# Schematics.net
KiCad netlist of a schematic drawn in Altium Designer
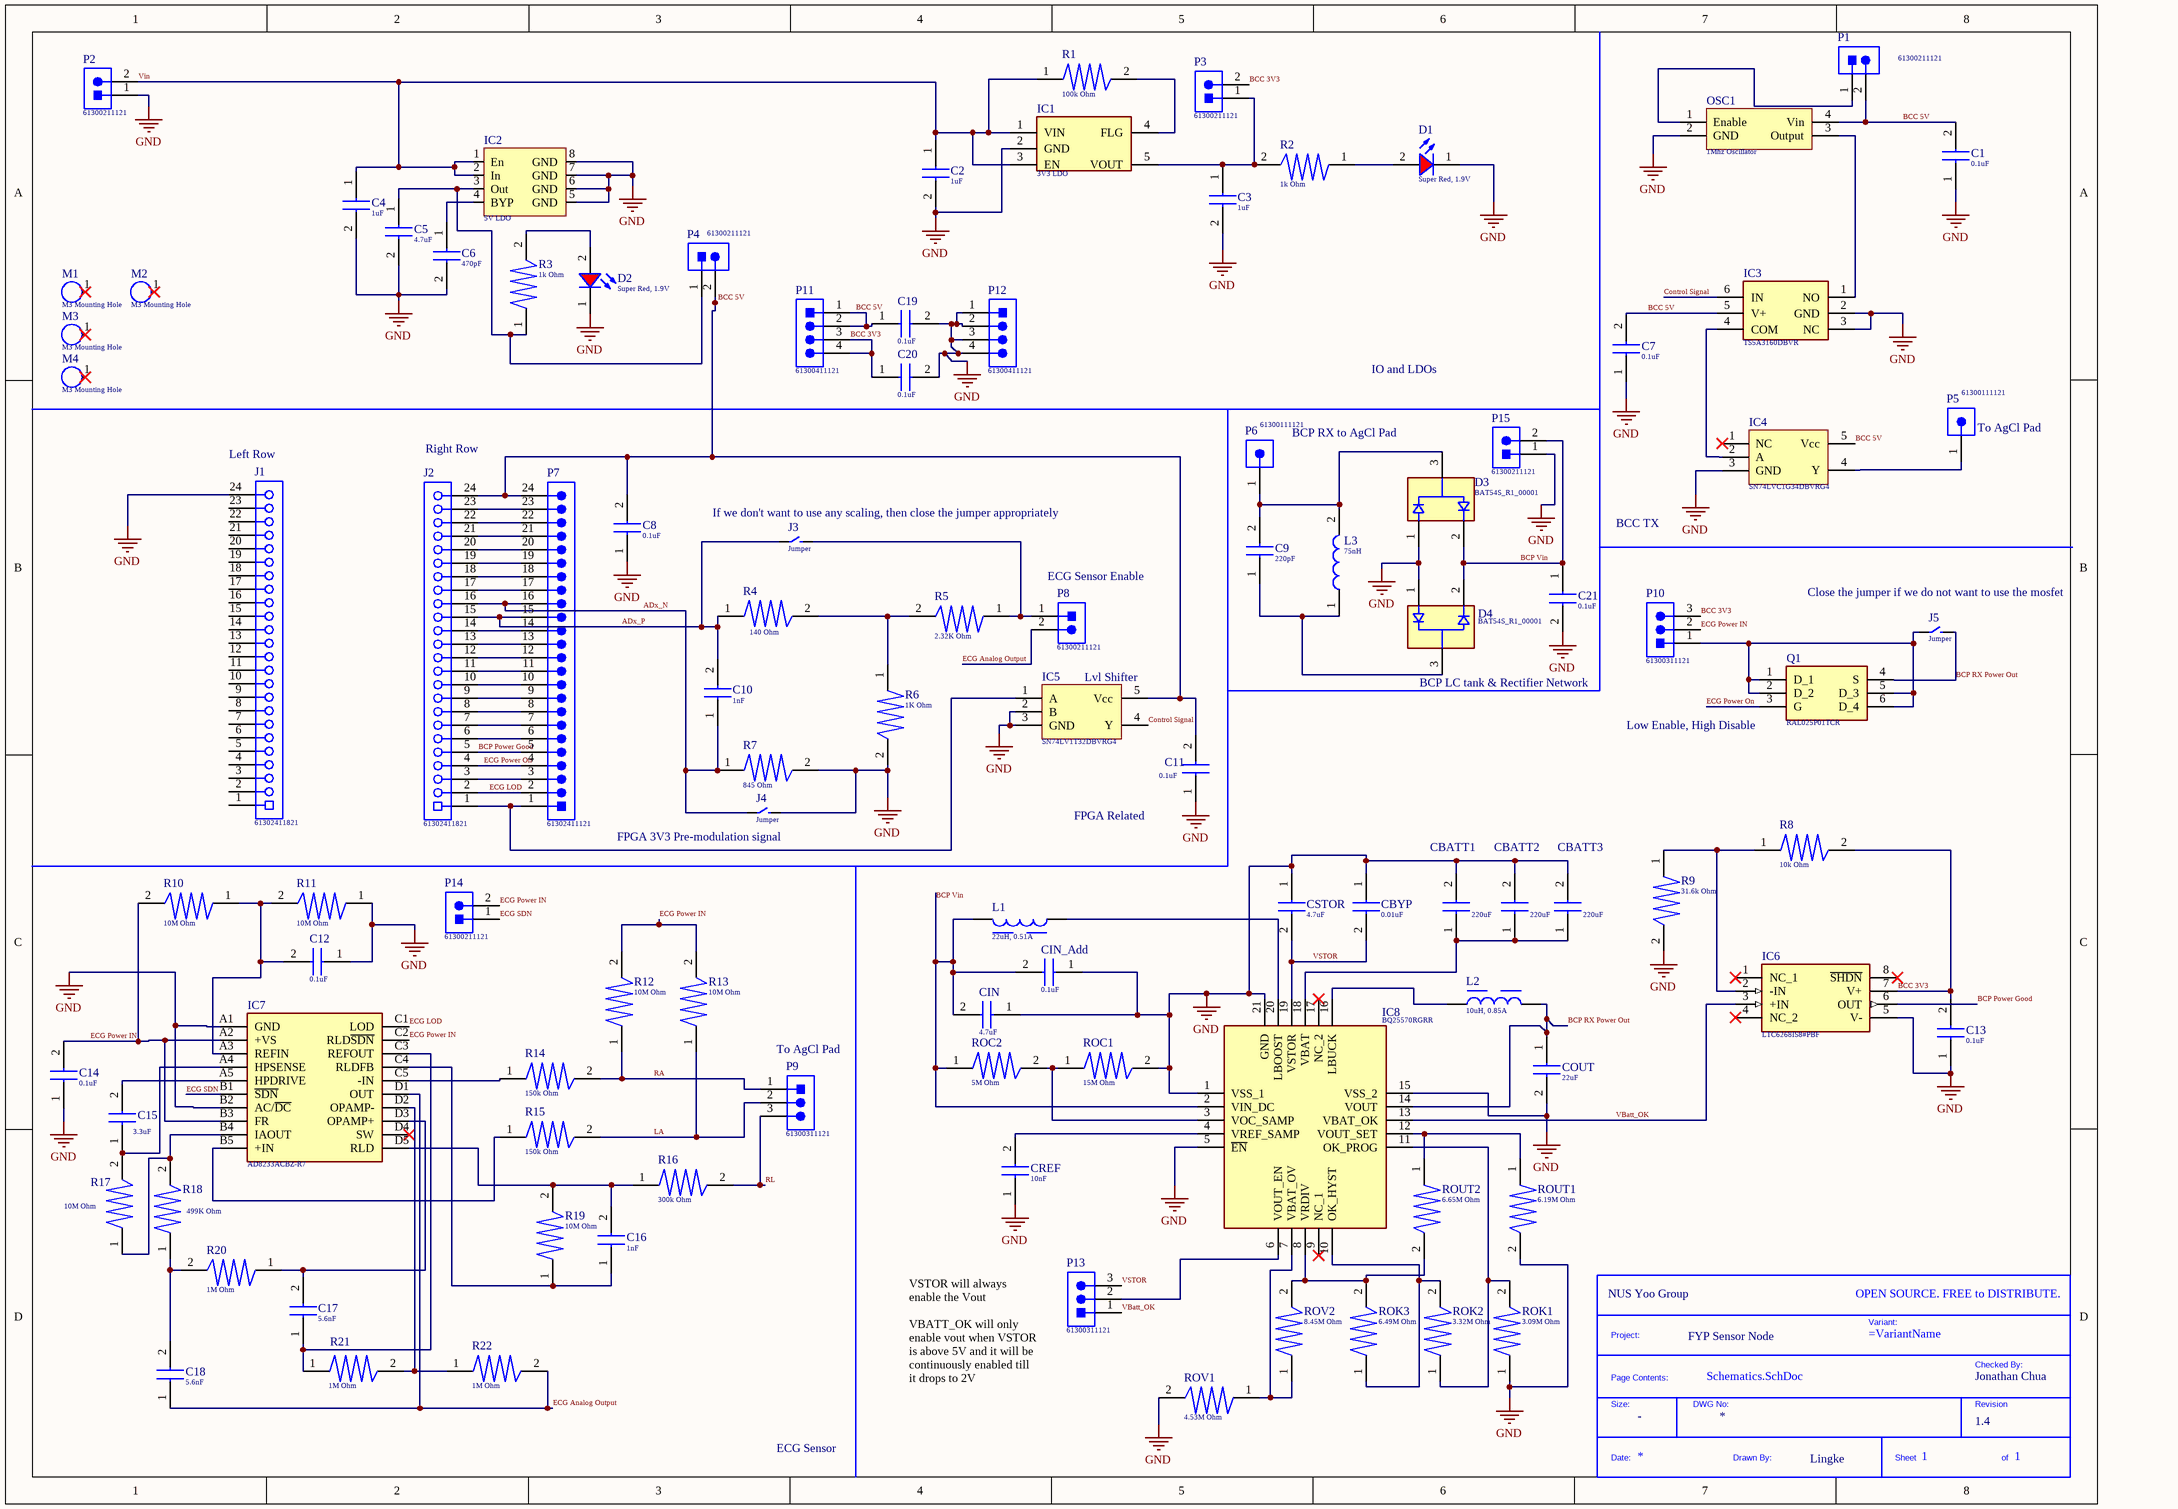
[diagram p0: Schematics.SchDoc]

(export (version "E")
  (design (tool "Eeschema 10.0.6"))
  (components
    (comp (ref "*")
      (value "Title_Block")
      (description "Standard Title Block.")
      (fields
        (field (name "PROJECT NAME") "FYP Sensor Node")
        (field (name "COMPANY") "NUS Yoo Group")
        (field (name "DRAWN BY") "Lingke")
        (field (name "REVISION") "1.4")
        (field (name "DWG NO") "*")
        (field (name "SIZE") "-")
        (field (name "CHECKED BY") "Jonathan Chua")
      )
      (libsource (lib "General Electronics") (part "Title_Block"))
    )
    (comp (ref "C1")
      (value "0.1uF")
      (footprint "0603")
      (description "Capacitor")
      (libsource (lib "General Electronics") (part "Capacitor_0603"))
    )
    (comp (ref "C2")
      (value "1uF")
      (footprint "0603")
      (description "Capacitor")
      (libsource (lib "General Electronics") (part "Capacitor_0603"))
    )
    (comp (ref "C3")
      (value "1uF")
      (footprint "0603")
      (description "Capacitor")
      (libsource (lib "General Electronics") (part "Capacitor_0603"))
    )
    (comp (ref "C4")
      (value "1uF")
      (footprint "0603")
      (description "Capacitor")
      (libsource (lib "General Electronics") (part "Capacitor_0603"))
    )
    (comp (ref "C5")
      (value "4.7uF")
      (footprint "0603")
      (description "Capacitor")
      (libsource (lib "General Electronics") (part "Capacitor_0603"))
    )
    (comp (ref "C6")
      (value "470pF")
      (footprint "0603")
      (description "Capacitor")
      (libsource (lib "General Electronics") (part "Capacitor_0603"))
    )
    (comp (ref "C7")
      (value "0.1uF")
      (footprint "0603")
      (description "Capacitor")
      (libsource (lib "General Electronics") (part "Capacitor_0603"))
    )
    (comp (ref "C8")
      (value "0.1uF")
      (footprint "0603")
      (description "Capacitor")
      (libsource (lib "General Electronics") (part "Capacitor_0603"))
    )
    (comp (ref "C9")
      (value "220pF")
      (footprint "0603")
      (description "Capacitor")
      (libsource (lib "General Electronics") (part "Capacitor_0603"))
    )
    (comp (ref "C10")
      (value "1nF")
      (footprint "0603")
      (description "Capacitor")
      (libsource (lib "General Electronics") (part "Capacitor_0603"))
    )
    (comp (ref "C11")
      (value "0.1uF")
      (footprint "0603")
      (description "Capacitor")
      (libsource (lib "General Electronics") (part "Capacitor_0603"))
    )
    (comp (ref "C12")
      (value "0.1uF")
      (footprint "0603")
      (description "Capacitor")
      (libsource (lib "General Electronics") (part "Capacitor_0603"))
    )
    (comp (ref "C13")
      (value "0.1uF")
      (footprint "0603")
      (description "Capacitor")
      (libsource (lib "General Electronics") (part "Capacitor_0603"))
    )
    (comp (ref "C14")
      (value "0.1uF")
      (footprint "0603")
      (description "Capacitor")
      (libsource (lib "General Electronics") (part "Capacitor_0603"))
    )
    (comp (ref "C15")
      (value "3.3uF")
      (footprint "0603")
      (description "Capacitor")
      (libsource (lib "General Electronics") (part "Capacitor_0603"))
    )
    (comp (ref "C16")
      (value "1nF")
      (footprint "0603")
      (description "Capacitor")
      (libsource (lib "General Electronics") (part "Capacitor_0603"))
    )
    (comp (ref "C17")
      (value "5.6nF")
      (footprint "0603")
      (description "Capacitor")
      (libsource (lib "General Electronics") (part "Capacitor_0603"))
    )
    (comp (ref "C18")
      (value "5.6nF")
      (footprint "0603")
      (description "Capacitor")
      (libsource (lib "General Electronics") (part "Capacitor_0603"))
    )
    (comp (ref "C19")
      (value "0.1uF")
      (footprint "0603")
      (description "Capacitor")
      (libsource (lib "General Electronics") (part "Capacitor_0603"))
    )
    (comp (ref "C20")
      (value "0.1uF")
      (footprint "0603")
      (description "Capacitor")
      (libsource (lib "General Electronics") (part "Capacitor_0603"))
    )
    (comp (ref "C21")
      (value "0.1uF")
      (footprint "0603")
      (description "Capacitor")
      (libsource (lib "General Electronics") (part "Capacitor_0603"))
    )
    (comp (ref "CBATT1")
      (value "220uF")
      (footprint "1206")
      (description "Capacitor")
      (libsource (lib "General Electronics") (part "Capacitor_1206"))
    )
    (comp (ref "CBATT2")
      (value "220uF")
      (footprint "1206")
      (description "Capacitor")
      (libsource (lib "General Electronics") (part "Capacitor_1206"))
    )
    (comp (ref "CBATT3")
      (value "220uF")
      (footprint "1206")
      (description "Capacitor")
      (libsource (lib "General Electronics") (part "Capacitor_1206"))
    )
    (comp (ref "CBYP")
      (value "0.01uF")
      (footprint "0603")
      (description "Capacitor")
      (libsource (lib "General Electronics") (part "Capacitor_0603"))
    )
    (comp (ref "CIN")
      (value "4.7uF")
      (footprint "0603")
      (description "Capacitor")
      (libsource (lib "General Electronics") (part "Capacitor_0603"))
    )
    (comp (ref "CIN_Add")
      (value "0.1uF")
      (footprint "0603")
      (description "Capacitor")
      (libsource (lib "General Electronics") (part "Capacitor_0603"))
    )
    (comp (ref "COUT")
      (value "22uF")
      (footprint "0603")
      (description "Capacitor")
      (libsource (lib "General Electronics") (part "Capacitor_0603"))
    )
    (comp (ref "CREF")
      (value "10nF")
      (footprint "0603")
      (description "Capacitor")
      (libsource (lib "General Electronics") (part "Capacitor_0603"))
    )
    (comp (ref "CSTOR")
      (value "4.7uF")
      (footprint "0603")
      (description "Capacitor")
      (libsource (lib "General Electronics") (part "Capacitor_0603"))
    )
    (comp (ref "D1")
      (value "Super Red, 1.9V")
      (footprint "WL-SMCW_0603_H=0.7mm")
      (description "WL-SMCW SMT Mono-color Chip LED Waterclear, size 0603, Super Red, 1.9V, 140deg")
      (fields (field (name "PART NUMBER") "150060SS75000") (field (name "PUBLISHER") "Wurth Elektronik"))
      (libsource (lib "Altium_WL-SMCW (rev20a)") (part "150060SS75000"))
    )
    (comp (ref "D2")
      (value "Super Red, 1.9V")
      (footprint "WL-SMCW_0603_H=0.7mm")
      (description "WL-SMCW SMT Mono-color Chip LED Waterclear, size 0603, Super Red, 1.9V, 140deg")
      (fields (field (name "PART NUMBER") "150060SS75000") (field (name "PUBLISHER") "Wurth Elektronik"))
      (libsource (lib "Altium_WL-SMCW (rev20a)") (part "150060SS75000"))
    )
    (comp (ref "D3")
      (value "BAT54S_R1_00001")
      (footprint "SOT95P240X110-3N")
      (description "Schottky Diode")
      (libsource (lib "") (part "BAT54S_R1_00001_1"))
    )
    (comp (ref "D4")
      (value "BAT54S_R1_00001")
      (footprint "SOT95P240X110-3N")
      (description "Schottky Diode")
      (libsource (lib "FYP_BCC_BCP NUS") (part "BAT54S_R1_00001"))
    )
    (comp (ref "IC1")
      (value "3V3 LDO")
      (footprint "SOT-23-5")
      (description "Power Supply")
      (fields
        (field (name "MOUSER2 PART NUMBER") "998-MIC5317-3.3YM5TR")
        (field (name "MANUFACTURER_PART_NUMBER") "MIC5317-3.3YM5-TR")
      )
      (libsource (lib "FYP_BCC_BCP NUS") (part "MIC5216-3.3YM5-TR"))
    )
    (comp (ref "IC2")
      (value "5V LDO")
      (footprint "MSOP-8_MS")
      (libsource (lib "FYP_BCC_BCP NUS") (part "MIC5219-5.0YMM-TR"))
    )
    (comp (ref "IC3")
      (value "TS5A3160DBVR")
      (footprint "SOT-23-6")
      (description "Integrated Circuit")
      (fields (field (name "MOUSER2 PART NUMBER") "595-TS5A3160DBVR"))
      (libsource (lib "FYP_BCC_BCP NUS") (part "TS5A3160DBVR"))
    )
    (comp (ref "IC4")
      (value "SN74LVC1G34DBVRG4")
      (footprint "SOT-23-5")
      (libsource (lib "FYP_BCC_BCP NUS") (part "SN74LVC1G34DBVRG4"))
    )
    (comp (ref "IC5")
      (value "SN74LV1T32DBVRG4")
      (footprint "SOT-23-5")
      (libsource (lib "FYP_BCC_BCP NUS") (part "SN74LV1T32DBVRG4"))
    )
    (comp (ref "IC6")
      (value "LTC6268IS8#PBF")
      (footprint "SOIC127P599X175-8N")
      (description "Integrated Circuit")
      (fields (field (name "MOUSER2 PART NUMBER") "584-LTC6268IS8#PBF"))
      (libsource (lib "FYP_BCC_BCP NUS") (part "LTC6268IS8#PBF"))
    )
    (comp (ref "IC7")
      (value "AD8233ACBZ-R7")
      (footprint "BGA20C40P5X4_204X170X56")
      (description "Integrated Circuit")
      (libsource (lib "FYP_BCC_BCP NUS") (part "AD8233ACBZ-R7"))
    )
    (comp (ref "IC8")
      (value "BQ25570RGRR")
      (footprint "QFN50P350X350X100-21N-D")
      (description "Integrated Circuit")
      (fields (field (name "MOUSER2 PART NUMBER") "595-BQ25570RGRR"))
      (libsource (lib "FYP_BCC_BCP NUS") (part "BQ25570RGRR"))
    )
    (comp (ref "J1")
      (value "61302411821")
      (footprint "61302411821")
      (description "WR-PHD Socket Header, THT, pitch 2.54mm, Single Row, Vertical, 24p")
      (fields (field (name "MANUFACTURER") "Wurth Elektronik"))
      (libsource (lib "Altium_WR-PHD (rev22a)") (part "61302411821"))
    )
    (comp (ref "J2")
      (value "61302411821")
      (footprint "61302411821")
      (description "WR-PHD Socket Header, THT, pitch 2.54mm, Single Row, Vertical, 24p")
      (fields (field (name "MANUFACTURER") "Wurth Elektronik"))
      (libsource (lib "Altium_WR-PHD (rev22a)") (part "61302411821"))
    )
    (comp (ref "J3")
      (value "Jumper")
      (footprint "0603")
      (description "Capacitor")
      (libsource (lib "General Electronics") (part "0603_Jumper"))
    )
    (comp (ref "J4")
      (value "Jumper")
      (footprint "0603")
      (description "Capacitor")
      (libsource (lib "General Electronics") (part "0603_Jumper"))
    )
    (comp (ref "J5")
      (value "Jumper")
      (footprint "0603")
      (description "Capacitor")
      (libsource (lib "General Electronics") (part "0603_Jumper"))
    )
    (comp (ref "L1")
      (value "22uH, 0.51A")
      (footprint "WE-TPC_3816")
      (description "WE-TPC SMT Tiny Power Inductor, size 3816, 22uH, 0.51A, 450mOhm")
      (fields
        (field (name "MANUFACTURER") "Wurth Elektronik")
        (field (name "MANUFACTURER PART NUMBER") "744031220")
      )
      (libsource (lib "WE-TPC (rev22a)") (part "744031220"))
    )
    (comp (ref "L2")
      (value "10uH, 0.85A")
      (footprint "WE-MAPI_3015")
      (description "WE-MAPI SMT Power Inductor, size 3015, 10uH, 0.85A")
      (fields
        (field (name "MANUFACTURER") "Wurth Elektronik")
        (field (name "MANUFACTURER PART NUMBER") "74438335100")
      )
      (libsource (lib "WE-MAPI (rev22a)") (part "74438335100"))
    )
    (comp (ref "L3")
      (value "75nH")
      (footprint "0603")
      (description "Inductor")
      (libsource (lib "General Electronics") (part "Inductor_0603"))
    )
    (comp (ref "M1")
      (value "M3 Mounting Hole")
      (footprint "M3 Hole")
      (libsource (lib "General Electronics") (part "M3_Mounting_hole"))
    )
    (comp (ref "M2")
      (value "M3 Mounting Hole")
      (footprint "M3 Hole")
      (libsource (lib "General Electronics") (part "M3_Mounting_hole"))
    )
    (comp (ref "M3")
      (value "M3 Mounting Hole")
      (footprint "M3 Hole")
      (libsource (lib "General Electronics") (part "M3_Mounting_hole"))
    )
    (comp (ref "M4")
      (value "M3 Mounting Hole")
      (footprint "M3 Hole")
      (libsource (lib "General Electronics") (part "M3_Mounting_hole"))
    )
    (comp (ref "OSC1")
      (value "1Mhz Oscillator")
      (footprint "CB3-3I-4M0000")
      (libsource (lib "FYP_BCC_BCP NUS") (part "LFSPXO053327Bulk"))
    )
    (comp (ref "P1")
      (value "61300211121")
      (footprint "61300211121")
      (description "WR-PHD Pin Header, THT, pitch 2.54mm, Single Row, Vertical, 2p")
      (fields (field (name "MANUFACTURER") "Wurth Elektronik"))
      (libsource (lib "") (part "61300211121_1"))
    )
    (comp (ref "P2")
      (value "61300211121")
      (footprint "61300211121")
      (description "WR-PHD Pin Header, THT, pitch 2.54mm, Single Row, Vertical, 2p")
      (fields (field (name "MANUFACTURER") "Wurth Elektronik"))
      (libsource (lib "Altium_WR-PHD (rev22a)") (part "61300211121"))
    )
    (comp (ref "P3")
      (value "61300211121")
      (footprint "61300211121")
      (description "WR-PHD Pin Header, THT, pitch 2.54mm, Single Row, Vertical, 2p")
      (fields (field (name "MANUFACTURER") "Wurth Elektronik"))
      (libsource (lib "Altium_WR-PHD (rev22a)") (part "61300211121"))
    )
    (comp (ref "P4")
      (value "61300211121")
      (footprint "61300211121")
      (description "WR-PHD Pin Header, THT, pitch 2.54mm, Single Row, Vertical, 2p")
      (fields (field (name "MANUFACTURER") "Wurth Elektronik"))
      (libsource (lib "") (part "61300211121_1"))
    )
    (comp (ref "P5")
      (value "61300111121")
      (footprint "61300111121")
      (description "WR-PHD Pin Header, THT, pitch 2.54mm, Single Row, Vertical, 1p")
      (fields (field (name "MANUFACTURER") "Wurth Elektronik"))
      (libsource (lib "Altium_WR-PHD (rev22a)") (part "61300111121"))
    )
    (comp (ref "P6")
      (value "61300111121")
      (footprint "61300111121")
      (description "WR-PHD Pin Header, THT, pitch 2.54mm, Single Row, Vertical, 1p")
      (fields (field (name "MANUFACTURER") "Wurth Elektronik"))
      (libsource (lib "Altium_WR-PHD (rev22a)") (part "61300111121"))
    )
    (comp (ref "P7")
      (value "61302411121")
      (footprint "61302411121")
      (description "WR-PHD Pin Header, THT, pitch 2.54mm, Single Row, Vertical, 24p")
      (fields (field (name "MANUFACTURER") "Wurth Elektronik"))
      (libsource (lib "Altium_WR-PHD (rev22a)") (part "61302411121"))
    )
    (comp (ref "P8")
      (value "61300211121")
      (footprint "61300211121")
      (description "WR-PHD Pin Header, THT, pitch 2.54mm, Single Row, Vertical, 2p")
      (fields (field (name "MANUFACTURER") "Wurth Elektronik"))
      (libsource (lib "") (part "61300211121_2"))
    )
    (comp (ref "P9")
      (value "61300311121")
      (footprint "61300311121")
      (description "WR-PHD Pin Header, THT, pitch 2.54mm, Single Row, Vertical, 3p")
      (fields (field (name "MANUFACTURER") "Wurth Elektronik"))
      (libsource (lib "") (part "61300311121_1"))
    )
    (comp (ref "P10")
      (value "61300311121")
      (footprint "61300311121")
      (description "WR-PHD Pin Header, THT, pitch 2.54mm, Single Row, Vertical, 3p")
      (fields (field (name "MANUFACTURER") "Wurth Elektronik"))
      (libsource (lib "Altium_WR-PHD (rev22a)") (part "61300311121"))
    )
    (comp (ref "P11")
      (value "61300411121")
      (footprint "61300411121")
      (description "WR-PHD Pin Header, THT, pitch 2.54mm, Single Row, Vertical, 4p")
      (fields (field (name "MANUFACTURER") "Wurth Elektronik"))
      (libsource (lib "Altium_WR-PHD (rev22a)") (part "61300411121"))
    )
    (comp (ref "P12")
      (value "61300411121")
      (footprint "61300411121")
      (description "WR-PHD Pin Header, THT, pitch 2.54mm, Single Row, Vertical, 4p")
      (fields (field (name "MANUFACTURER") "Wurth Elektronik"))
      (libsource (lib "") (part "61300411121_1"))
    )
    (comp (ref "P13")
      (value "61300311121")
      (footprint "61300311121")
      (description "WR-PHD Pin Header, THT, pitch 2.54mm, Single Row, Vertical, 3p")
      (fields (field (name "MANUFACTURER") "Wurth Elektronik"))
      (libsource (lib "Altium_WR-PHD (rev22a)") (part "61300311121"))
    )
    (comp (ref "P14")
      (value "61300211121")
      (footprint "61300211121")
      (description "WR-PHD Pin Header, THT, pitch 2.54mm, Single Row, Vertical, 2p")
      (fields (field (name "MANUFACTURER") "Wurth Elektronik"))
      (libsource (lib "Altium_WR-PHD (rev22a)") (part "61300211121"))
    )
    (comp (ref "P15")
      (value "61300211121")
      (footprint "61300211121")
      (description "WR-PHD Pin Header, THT, pitch 2.54mm, Single Row, Vertical, 2p")
      (fields (field (name "MANUFACTURER") "Wurth Elektronik"))
      (libsource (lib "Altium_WR-PHD (rev22a)") (part "61300211121"))
    )
    (comp (ref "Q1")
      (value "RAL025P01TCR")
      (footprint "RAL025P01TCR")
      (description "MOSFET (P-Channel)")
      (libsource (lib "FYP_BCC_BCP NUS") (part "RAL025P01TCR"))
    )
    (comp (ref "R1")
      (value "100k Ohm")
      (footprint "0603")
      (description "Resistor")
      (libsource (lib "General Electronics") (part "Resistor"))
    )
    (comp (ref "R2")
      (value "1k Ohm")
      (footprint "0603")
      (description "Resistor")
      (libsource (lib "General Electronics") (part "Resistor"))
    )
    (comp (ref "R3")
      (value "1k Ohm")
      (footprint "0603")
      (description "Resistor")
      (libsource (lib "General Electronics") (part "Resistor"))
    )
    (comp (ref "R4")
      (value "140 Ohm")
      (footprint "0603")
      (description "Resistor")
      (libsource (lib "General Electronics") (part "Resistor"))
    )
    (comp (ref "R5")
      (value "2.32K Ohm")
      (footprint "0603")
      (description "Resistor")
      (libsource (lib "General Electronics") (part "Resistor"))
    )
    (comp (ref "R6")
      (value "1K Ohm")
      (footprint "0603")
      (description "Resistor")
      (libsource (lib "General Electronics") (part "Resistor"))
    )
    (comp (ref "R7")
      (value "845 Ohm")
      (footprint "0603")
      (description "Resistor")
      (libsource (lib "General Electronics") (part "Resistor"))
    )
    (comp (ref "R8")
      (value "10k Ohm")
      (footprint "0603")
      (description "Resistor")
      (libsource (lib "General Electronics") (part "Resistor"))
    )
    (comp (ref "R9")
      (value "31.6k Ohm")
      (footprint "0603")
      (description "Resistor")
      (libsource (lib "General Electronics") (part "Resistor"))
    )
    (comp (ref "R10")
      (value "10M Ohm")
      (footprint "0603")
      (description "Resistor")
      (libsource (lib "General Electronics") (part "Resistor"))
    )
    (comp (ref "R11")
      (value "10M Ohm")
      (footprint "0603")
      (description "Resistor")
      (libsource (lib "General Electronics") (part "Resistor"))
    )
    (comp (ref "R12")
      (value "10M Ohm")
      (footprint "0603")
      (description "Resistor")
      (libsource (lib "General Electronics") (part "Resistor"))
    )
    (comp (ref "R13")
      (value "10M Ohm")
      (footprint "0603")
      (description "Resistor")
      (libsource (lib "General Electronics") (part "Resistor"))
    )
    (comp (ref "R14")
      (value "150k Ohm")
      (footprint "0603")
      (description "Resistor")
      (libsource (lib "General Electronics") (part "Resistor"))
    )
    (comp (ref "R15")
      (value "150k Ohm")
      (footprint "0603")
      (description "Resistor")
      (libsource (lib "General Electronics") (part "Resistor"))
    )
    (comp (ref "R16")
      (value "300k Ohm")
      (footprint "0603")
      (description "Resistor")
      (libsource (lib "General Electronics") (part "Resistor"))
    )
    (comp (ref "R17")
      (value "10M Ohm")
      (footprint "0603")
      (description "Resistor")
      (libsource (lib "General Electronics") (part "Resistor"))
    )
    (comp (ref "R18")
      (value "499K Ohm")
      (footprint "0603")
      (description "Resistor")
      (libsource (lib "General Electronics") (part "Resistor"))
    )
    (comp (ref "R19")
      (value "10M Ohm")
      (footprint "0603")
      (description "Resistor")
      (libsource (lib "General Electronics") (part "Resistor"))
    )
    (comp (ref "R20")
      (value "1M Ohm")
      (footprint "0603")
      (description "Resistor")
      (libsource (lib "General Electronics") (part "Resistor"))
    )
    (comp (ref "R21")
      (value "1M Ohm")
      (footprint "0603")
      (description "Resistor")
      (libsource (lib "General Electronics") (part "Resistor"))
    )
    (comp (ref "R22")
      (value "1M Ohm")
      (footprint "0603")
      (description "Resistor")
      (libsource (lib "General Electronics") (part "Resistor"))
    )
    (comp (ref "ROC1")
      (value "15M Ohm")
      (footprint "0603")
      (description "Resistor")
      (libsource (lib "General Electronics") (part "Resistor"))
    )
    (comp (ref "ROC2")
      (value "5M Ohm")
      (footprint "0603")
      (description "Resistor")
      (libsource (lib "General Electronics") (part "Resistor"))
    )
    (comp (ref "ROK1")
      (value "3.09M Ohm")
      (footprint "0603")
      (description "Resistor")
      (libsource (lib "General Electronics") (part "Resistor"))
    )
    (comp (ref "ROK2")
      (value "3.32M Ohm")
      (footprint "0603")
      (description "Resistor")
      (libsource (lib "General Electronics") (part "Resistor"))
    )
    (comp (ref "ROK3")
      (value "6.49M Ohm")
      (footprint "0603")
      (description "Resistor")
      (libsource (lib "General Electronics") (part "Resistor"))
    )
    (comp (ref "ROUT1")
      (value "6.19M Ohm")
      (footprint "0603")
      (description "Resistor")
      (libsource (lib "General Electronics") (part "Resistor"))
    )
    (comp (ref "ROUT2")
      (value "6.65M Ohm")
      (footprint "0603")
      (description "Resistor")
      (libsource (lib "General Electronics") (part "Resistor"))
    )
    (comp (ref "ROV1")
      (value "4.53M Ohm")
      (footprint "0603")
      (description "Resistor")
      (libsource (lib "General Electronics") (part "Resistor"))
    )
    (comp (ref "ROV2")
      (value "8.45M Ohm")
      (footprint "0603")
      (description "Resistor")
      (libsource (lib "General Electronics") (part "Resistor"))
    )
  )
  (nets
    (net (code "1") (name "/ADx_N") (class "Default")
      (node (ref "C10") (pin "1") (pinfunction "1_1") (pintype "passive"))
      (node (ref "J2") (pin "16") (pinfunction "16_16") (pintype "passive"))
      (node (ref "J4") (pin "1") (pinfunction "1_1") (pintype "passive"))
      (node (ref "P7") (pin "16") (pinfunction "16_16") (pintype "passive"))
      (node (ref "R7") (pin "1") (pintype "passive"))
    )
    (net (code "2") (name "/ADx_P") (class "Default")
      (node (ref "C10") (pin "2") (pinfunction "2_2") (pintype "passive"))
      (node (ref "J2") (pin "15") (pinfunction "15_15") (pintype "passive"))
      (node (ref "J3") (pin "1") (pinfunction "1_1") (pintype "passive"))
      (node (ref "P7") (pin "15") (pinfunction "15_15") (pintype "passive"))
      (node (ref "R4") (pin "1") (pintype "passive"))
    )
    (net (code "3") (name "/BCC 3V3") (class "Default")
      (node (ref "C13") (pin "2") (pinfunction "2_2") (pintype "passive"))
      (node (ref "C20") (pin "1") (pinfunction "1_1") (pintype "passive"))
      (node (ref "IC6") (pin "7") (pinfunction "V+_7") (pintype "passive"))
      (node (ref "P10") (pin "3") (pinfunction "3_3") (pintype "passive"))
      (node (ref "P11") (pin "3") (pinfunction "3_3") (pintype "passive"))
      (node (ref "P11") (pin "4") (pinfunction "4_4") (pintype "passive"))
      (node (ref "P3") (pin "2") (pinfunction "2_2") (pintype "passive"))
      (node (ref "R8") (pin "2") (pintype "passive"))
    )
    (net (code "4") (name "/BCC 5V") (class "Default")
      (node (ref "C1") (pin "2") (pinfunction "2_2") (pintype "passive"))
      (node (ref "C11") (pin "2") (pinfunction "2_2") (pintype "passive"))
      (node (ref "C19") (pin "1") (pinfunction "1_1") (pintype "passive"))
      (node (ref "C7") (pin "2") (pinfunction "2_2") (pintype "passive"))
      (node (ref "C8") (pin "2") (pinfunction "2_2") (pintype "passive"))
      (node (ref "IC3") (pin "5") (pinfunction "V+_5") (pintype "passive"))
      (node (ref "IC4") (pin "5") (pinfunction "Vcc_5") (pintype "passive"))
      (node (ref "IC5") (pin "5") (pinfunction "Vcc_5") (pintype "passive"))
      (node (ref "J2") (pin "24") (pinfunction "24_24") (pintype "passive"))
      (node (ref "OSC1") (pin "4") (pinfunction "Vin_4") (pintype "passive"))
      (node (ref "P1") (pin "2") (pinfunction "2_2") (pintype "passive"))
      (node (ref "P11") (pin "1") (pinfunction "1_1") (pintype "passive"))
      (node (ref "P11") (pin "2") (pinfunction "2_2") (pintype "passive"))
      (node (ref "P4") (pin "2") (pinfunction "2_2") (pintype "passive"))
      (node (ref "P7") (pin "24") (pinfunction "24_24") (pintype "passive"))
    )
    (net (code "5") (name "/BCP Power Good") (class "Default")
      (node (ref "IC6") (pin "6") (pinfunction "OUT_6") (pintype "output"))
      (node (ref "J2") (pin "5") (pinfunction "5_5") (pintype "passive"))
      (node (ref "P7") (pin "5") (pinfunction "5_5") (pintype "passive"))
    )
    (net (code "6") (name "/BCP RX Power Out") (class "Default")
      (node (ref "COUT") (pin "1") (pinfunction "1_1") (pintype "passive"))
      (node (ref "IC8") (pin "14") (pinfunction "VOUT_14") (pintype "passive"))
      (node (ref "J5") (pin "2") (pinfunction "2_2") (pintype "passive"))
      (node (ref "L2") (pin "2") (pinfunction "2_2") (pintype "passive"))
      (node (ref "Q1") (pin "4") (pinfunction "S_4") (pintype "passive"))
    )
    (net (code "7") (name "/BCP Vin") (class "Default")
      (node (ref "C21") (pin "1") (pinfunction "1_1") (pintype "passive"))
      (node (ref "CIN") (pin "2") (pinfunction "2_2") (pintype "passive"))
      (node (ref "CIN_Add") (pin "2") (pinfunction "2_2") (pintype "passive"))
      (node (ref "D3") (pin "2") (pinfunction "K_2") (pintype "passive"))
      (node (ref "D4") (pin "2") (pinfunction "K_2") (pintype "passive"))
      (node (ref "IC8") (pin "2") (pinfunction "VIN_DC_2") (pintype "passive"))
      (node (ref "L1") (pin "2") (pinfunction "2_2") (pintype "passive"))
      (node (ref "P15") (pin "2") (pinfunction "2_2") (pintype "passive"))
      (node (ref "ROC2") (pin "1") (pintype "passive"))
    )
    (net (code "8") (name "/Control Signal") (class "Default")
      (node (ref "IC3") (pin "6") (pinfunction "IN_6") (pintype "passive"))
      (node (ref "IC5") (pin "4") (pinfunction "Y_4") (pintype "passive"))
    )
    (net (code "9") (name "/ECG Analog Output") (class "Default")
      (node (ref "C18") (pin "1") (pinfunction "1_1") (pintype "passive"))
      (node (ref "IC7") (pin "D1") (pinfunction "OUT_D1") (pintype "passive"))
      (node (ref "P8") (pin "2") (pinfunction "2_2") (pintype "passive"))
      (node (ref "R22") (pin "2") (pintype "passive"))
    )
    (net (code "10") (name "/ECG LOD") (class "Default")
      (node (ref "IC7") (pin "C1") (pinfunction "LOD_C1") (pintype "passive"))
      (node (ref "J2") (pin "2") (pinfunction "2_2") (pintype "passive"))
      (node (ref "P7") (pin "2") (pinfunction "2_2") (pintype "passive"))
    )
    (net (code "11") (name "/ECG Power IN") (class "Default")
      (node (ref "C14") (pin "2") (pinfunction "2_2") (pintype "passive"))
      (node (ref "IC7") (pin "A2") (pinfunction "+VS_A2") (pintype "passive"))
      (node (ref "IC7") (pin "B3") (pinfunction "FR_B3") (pintype "passive"))
      (node (ref "IC7") (pin "C2") (pinfunction "RLD~{SDN}_C2") (pintype "passive"))
      (node (ref "P10") (pin "2") (pinfunction "2_2") (pintype "passive"))
      (node (ref "P14") (pin "2") (pinfunction "2_2") (pintype "passive"))
      (node (ref "R10") (pin "2") (pintype "passive"))
      (node (ref "R12") (pin "2") (pintype "passive"))
      (node (ref "R13") (pin "2") (pintype "passive"))
    )
    (net (code "12") (name "/ECG Power On") (class "Default")
      (node (ref "J2") (pin "4") (pinfunction "4_4") (pintype "passive"))
      (node (ref "P7") (pin "4") (pinfunction "4_4") (pintype "passive"))
      (node (ref "Q1") (pin "3") (pinfunction "G_3") (pintype "passive"))
    )
    (net (code "13") (name "/ECG SDN") (class "Default")
      (node (ref "IC7") (pin "B1") (pinfunction "~{SDN}_B1") (pintype "passive"))
      (node (ref "P14") (pin "1") (pinfunction "1_1") (pintype "passive"))
    )
    (net (code "14") (name "/LA") (class "Default")
      (node (ref "P9") (pin "2") (pinfunction "2_2") (pintype "passive"))
      (node (ref "R13") (pin "1") (pintype "passive"))
      (node (ref "R15") (pin "2") (pintype "passive"))
    )
    (net (code "15") (name "/RA") (class "Default")
      (node (ref "P9") (pin "1") (pinfunction "1_1") (pintype "passive"))
      (node (ref "R12") (pin "1") (pintype "passive"))
      (node (ref "R14") (pin "2") (pintype "passive"))
    )
    (net (code "16") (name "/RL") (class "Default")
      (node (ref "P9") (pin "3") (pinfunction "3_3") (pintype "passive"))
      (node (ref "R16") (pin "2") (pintype "passive"))
    )
    (net (code "17") (name "/VBatt_OK") (class "Default")
      (node (ref "IC6") (pin "3") (pinfunction "+IN_3") (pintype "input"))
      (node (ref "IC8") (pin "13") (pinfunction "VBAT_OK_13") (pintype "passive"))
      (node (ref "P13") (pin "1") (pinfunction "1_1") (pintype "passive"))
    )
    (net (code "18") (name "/VSTOR") (class "Default")
      (node (ref "CBYP") (pin "2") (pinfunction "2_2") (pintype "passive"))
      (node (ref "CSTOR") (pin "2") (pinfunction "2_2") (pintype "passive"))
      (node (ref "IC8") (pin "19") (pinfunction "VSTOR_19") (pintype "passive"))
      (node (ref "P13") (pin "3") (pinfunction "3_3") (pintype "passive"))
    )
    (net (code "19") (name "/Vin") (class "Default")
      (node (ref "C2") (pin "1") (pinfunction "1_1") (pintype "passive"))
      (node (ref "C4") (pin "1") (pinfunction "1_1") (pintype "passive"))
      (node (ref "IC1") (pin "1") (pinfunction "VIN_1") (pintype "passive"))
      (node (ref "IC1") (pin "3") (pinfunction "EN_3") (pintype "passive"))
      (node (ref "IC2") (pin "1") (pinfunction "En_1") (pintype "passive"))
      (node (ref "IC2") (pin "2") (pinfunction "In_2") (pintype "passive"))
      (node (ref "P2") (pin "2") (pinfunction "2_2") (pintype "passive"))
      (node (ref "R1") (pin "1") (pintype "passive"))
    )
    (net (code "20") (name "GND") (class "Default")
      (node (ref "C1") (pin "1") (pinfunction "1_1") (pintype "passive"))
      (node (ref "C11") (pin "1") (pinfunction "1_1") (pintype "passive"))
      (node (ref "C12") (pin "1") (pinfunction "1_1") (pintype "passive"))
      (node (ref "C13") (pin "1") (pinfunction "1_1") (pintype "passive"))
      (node (ref "C14") (pin "1") (pinfunction "1_1") (pintype "passive"))
      (node (ref "C19") (pin "2") (pinfunction "2_2") (pintype "passive"))
      (node (ref "C2") (pin "2") (pinfunction "2_2") (pintype "passive"))
      (node (ref "C20") (pin "2") (pinfunction "2_2") (pintype "passive"))
      (node (ref "C21") (pin "2") (pinfunction "2_2") (pintype "passive"))
      (node (ref "C3") (pin "2") (pinfunction "2_2") (pintype "passive"))
      (node (ref "C4") (pin "2") (pinfunction "2_2") (pintype "passive"))
      (node (ref "C5") (pin "2") (pinfunction "2_2") (pintype "passive"))
      (node (ref "C6") (pin "2") (pinfunction "2_2") (pintype "passive"))
      (node (ref "C7") (pin "1") (pinfunction "1_1") (pintype "passive"))
      (node (ref "C8") (pin "1") (pinfunction "1_1") (pintype "passive"))
      (node (ref "CBATT1") (pin "2") (pinfunction "2_2") (pintype "passive"))
      (node (ref "CBATT2") (pin "2") (pinfunction "2_2") (pintype "passive"))
      (node (ref "CBATT3") (pin "2") (pinfunction "2_2") (pintype "passive"))
      (node (ref "CBYP") (pin "1") (pinfunction "1_1") (pintype "passive"))
      (node (ref "CIN") (pin "1") (pinfunction "1_1") (pintype "passive"))
      (node (ref "CIN_Add") (pin "1") (pinfunction "1_1") (pintype "passive"))
      (node (ref "COUT") (pin "2") (pinfunction "2_2") (pintype "passive"))
      (node (ref "CREF") (pin "1") (pinfunction "1_1") (pintype "passive"))
      (node (ref "CSTOR") (pin "1") (pinfunction "1_1") (pintype "passive"))
      (node (ref "D1") (pin "1") (pinfunction "K_1") (pintype "passive"))
      (node (ref "D2") (pin "1") (pinfunction "K_1") (pintype "passive"))
      (node (ref "D3") (pin "1") (pinfunction "A_1") (pintype "passive"))
      (node (ref "D4") (pin "1") (pinfunction "A_1") (pintype "passive"))
      (node (ref "IC1") (pin "2") (pinfunction "GND_2") (pintype "passive"))
      (node (ref "IC2") (pin "5") (pinfunction "GND_5") (pintype "passive"))
      (node (ref "IC2") (pin "6") (pinfunction "GND_6") (pintype "passive"))
      (node (ref "IC2") (pin "7") (pinfunction "GND_7") (pintype "passive"))
      (node (ref "IC2") (pin "8") (pinfunction "GND_8") (pintype "passive"))
      (node (ref "IC3") (pin "2") (pinfunction "GND_2") (pintype "passive"))
      (node (ref "IC3") (pin "3") (pinfunction "NC_3") (pintype "passive"))
      (node (ref "IC4") (pin "3") (pinfunction "GND_3") (pintype "passive"))
      (node (ref "IC5") (pin "2") (pinfunction "B_2") (pintype "passive"))
      (node (ref "IC5") (pin "3") (pinfunction "GND_3") (pintype "passive"))
      (node (ref "IC6") (pin "5") (pinfunction "V-_5") (pintype "passive"))
      (node (ref "IC7") (pin "A1") (pinfunction "GND_A1") (pintype "passive"))
      (node (ref "IC7") (pin "B2") (pinfunction "AC/~{DC}_B2") (pintype "passive"))
      (node (ref "IC8") (pin "1") (pinfunction "VSS_1_1") (pintype "passive"))
      (node (ref "IC8") (pin "15") (pinfunction "VSS_2_15") (pintype "passive"))
      (node (ref "IC8") (pin "21") (pinfunction "GND_21") (pintype "passive"))
      (node (ref "IC8") (pin "5") (pinfunction "~{EN}_5") (pintype "passive"))
      (node (ref "J1") (pin "24") (pinfunction "24_24") (pintype "passive"))
      (node (ref "J4") (pin "2") (pinfunction "2_2") (pintype "passive"))
      (node (ref "OSC1") (pin "2") (pinfunction "GND_2") (pintype "passive"))
      (node (ref "P12") (pin "1") (pinfunction "1_1") (pintype "passive"))
      (node (ref "P12") (pin "2") (pinfunction "2_2") (pintype "passive"))
      (node (ref "P12") (pin "3") (pinfunction "3_3") (pintype "passive"))
      (node (ref "P12") (pin "4") (pinfunction "4_4") (pintype "passive"))
      (node (ref "P15") (pin "1") (pinfunction "1_1") (pintype "passive"))
      (node (ref "P2") (pin "1") (pinfunction "1_1") (pintype "passive"))
      (node (ref "R11") (pin "1") (pintype "passive"))
      (node (ref "R6") (pin "2") (pintype "passive"))
      (node (ref "R7") (pin "2") (pintype "passive"))
      (node (ref "R9") (pin "2") (pintype "passive"))
      (node (ref "ROC1") (pin "2") (pintype "passive"))
      (node (ref "ROK1") (pin "1") (pintype "passive"))
      (node (ref "ROUT1") (pin "2") (pintype "passive"))
      (node (ref "ROV1") (pin "2") (pintype "passive"))
    )
    (net (code "21") (name "Net-(C18-Pad2)") (class "Default")
      (node (ref "C18") (pin "2") (pinfunction "2_2") (pintype "passive"))
      (node (ref "R18") (pin "1") (pintype "passive"))
      (node (ref "R20") (pin "2") (pintype "passive"))
    )
    (net (code "22") (name "Net-(D1-A)") (class "Default")
      (node (ref "D1") (pin "2") (pinfunction "A_2") (pintype "passive"))
      (node (ref "R2") (pin "1") (pintype "passive"))
    )
    (net (code "23") (name "Net-(D2-A)") (class "Default")
      (node (ref "D2") (pin "2") (pinfunction "A_2") (pintype "passive"))
      (node (ref "R3") (pin "2") (pintype "passive"))
    )
    (net (code "24") (name "Net-(D3-A{slash}K)") (class "Default")
      (node (ref "C9") (pin "2") (pinfunction "2_2") (pintype "passive"))
      (node (ref "D3") (pin "3") (pinfunction "A/K_3") (pintype "passive"))
      (node (ref "L3") (pin "2") (pinfunction "2_2") (pintype "passive"))
      (node (ref "P6") (pin "1") (pinfunction "1_1") (pintype "passive"))
    )
    (net (code "25") (name "Net-(D4-A{slash}K)") (class "Default")
      (node (ref "C9") (pin "1") (pinfunction "1_1") (pintype "passive"))
      (node (ref "D4") (pin "3") (pinfunction "A/K_3") (pintype "passive"))
      (node (ref "L3") (pin "1") (pinfunction "1_1") (pintype "passive"))
    )
    (net (code "26") (name "Net-(IC1-FLG)") (class "Default")
      (node (ref "IC1") (pin "4") (pinfunction "FLG_4") (pintype "passive"))
      (node (ref "R1") (pin "2") (pintype "passive"))
    )
    (net (code "27") (name "Net-(IC1-VOUT)") (class "Default")
      (node (ref "C3") (pin "1") (pinfunction "1_1") (pintype "passive"))
      (node (ref "IC1") (pin "5") (pinfunction "VOUT_5") (pintype "passive"))
      (node (ref "P3") (pin "1") (pinfunction "1_1") (pintype "passive"))
      (node (ref "R2") (pin "2") (pintype "passive"))
    )
    (net (code "28") (name "Net-(IC2-BYP)") (class "Default")
      (node (ref "C6") (pin "1") (pinfunction "1_1") (pintype "passive"))
      (node (ref "IC2") (pin "4") (pinfunction "BYP_4") (pintype "passive"))
    )
    (net (code "29") (name "Net-(IC2-Out)") (class "Default")
      (node (ref "C5") (pin "1") (pinfunction "1_1") (pintype "passive"))
      (node (ref "IC2") (pin "3") (pinfunction "Out_3") (pintype "passive"))
      (node (ref "P4") (pin "1") (pinfunction "1_1") (pintype "passive"))
      (node (ref "R3") (pin "1") (pintype "passive"))
    )
    (net (code "30") (name "Net-(IC3-COM)") (class "Default")
      (node (ref "IC3") (pin "4") (pinfunction "COM_4") (pintype "passive"))
      (node (ref "IC4") (pin "2") (pinfunction "A_2") (pintype "passive"))
    )
    (net (code "31") (name "Net-(IC3-NO)") (class "Default")
      (node (ref "IC3") (pin "1") (pinfunction "NO_1") (pintype "passive"))
      (node (ref "OSC1") (pin "3") (pinfunction "Output_3") (pintype "passive"))
    )
    (net (code "32") (name "Net-(IC4-Y)") (class "Default")
      (node (ref "IC4") (pin "4") (pinfunction "Y_4") (pintype "passive"))
      (node (ref "P5") (pin "1") (pinfunction "1_1") (pintype "passive"))
    )
    (net (code "33") (name "Net-(IC5-A)") (class "Default")
      (node (ref "IC5") (pin "1") (pinfunction "A_1") (pintype "passive"))
      (node (ref "J2") (pin "1") (pinfunction "1_1") (pintype "passive"))
      (node (ref "P7") (pin "1") (pinfunction "1_1") (pintype "passive"))
    )
    (net (code "34") (name "Net-(IC6--IN)") (class "Default")
      (node (ref "IC6") (pin "2") (pinfunction "-IN_2") (pintype "input"))
      (node (ref "R8") (pin "1") (pintype "passive"))
      (node (ref "R9") (pin "1") (pintype "passive"))
    )
    (net (code "35") (name "Net-(IC7-+IN)") (class "Default")
      (node (ref "IC7") (pin "B5") (pinfunction "+IN_B5") (pintype "passive"))
      (node (ref "R15") (pin "1") (pintype "passive"))
    )
    (net (code "36") (name "Net-(IC7--IN)") (class "Default")
      (node (ref "IC7") (pin "C5") (pinfunction "-IN_C5") (pintype "passive"))
      (node (ref "R14") (pin "1") (pintype "passive"))
    )
    (net (code "37") (name "Net-(IC7-HPDRIVE)") (class "Default")
      (node (ref "C15") (pin "2") (pinfunction "2_2") (pintype "passive"))
      (node (ref "IC7") (pin "A5") (pinfunction "HPDRIVE_A5") (pintype "passive"))
    )
    (net (code "38") (name "Net-(IC7-HPSENSE)") (class "Default")
      (node (ref "C15") (pin "1") (pinfunction "1_1") (pintype "passive"))
      (node (ref "IC7") (pin "A4") (pinfunction "HPSENSE_A4") (pintype "passive"))
      (node (ref "R17") (pin "2") (pintype "passive"))
    )
    (net (code "39") (name "Net-(IC7-IAOUT)") (class "Default")
      (node (ref "IC7") (pin "B4") (pinfunction "IAOUT_B4") (pintype "passive"))
      (node (ref "R17") (pin "1") (pintype "passive"))
      (node (ref "R18") (pin "2") (pintype "passive"))
    )
    (net (code "40") (name "Net-(IC7-OPAMP+)") (class "Default")
      (node (ref "C17") (pin "2") (pinfunction "2_2") (pintype "passive"))
      (node (ref "IC7") (pin "D3") (pinfunction "OPAMP+_D3") (pintype "passive"))
      (node (ref "R20") (pin "1") (pintype "passive"))
    )
    (net (code "41") (name "Net-(IC7-OPAMP-)") (class "Default")
      (node (ref "IC7") (pin "D2") (pinfunction "OPAMP-_D2") (pintype "passive"))
      (node (ref "R21") (pin "2") (pintype "passive"))
      (node (ref "R22") (pin "1") (pintype "passive"))
    )
    (net (code "42") (name "Net-(IC7-REFIN)") (class "Default")
      (node (ref "C12") (pin "2") (pinfunction "2_2") (pintype "passive"))
      (node (ref "IC7") (pin "A3") (pinfunction "REFIN_A3") (pintype "passive"))
      (node (ref "R10") (pin "1") (pintype "passive"))
      (node (ref "R11") (pin "2") (pintype "passive"))
    )
    (net (code "43") (name "Net-(IC7-REFOUT)") (class "Default")
      (node (ref "C17") (pin "1") (pinfunction "1_1") (pintype "passive"))
      (node (ref "IC7") (pin "C3") (pinfunction "REFOUT_C3") (pintype "passive"))
      (node (ref "R21") (pin "1") (pintype "passive"))
    )
    (net (code "44") (name "Net-(IC7-RLD)") (class "Default")
      (node (ref "C16") (pin "2") (pinfunction "2_2") (pintype "passive"))
      (node (ref "IC7") (pin "D5") (pinfunction "RLD_D5") (pintype "passive"))
      (node (ref "R16") (pin "1") (pintype "passive"))
      (node (ref "R19") (pin "2") (pintype "passive"))
    )
    (net (code "45") (name "Net-(IC7-RLDFB)") (class "Default")
      (node (ref "C16") (pin "1") (pinfunction "1_1") (pintype "passive"))
      (node (ref "IC7") (pin "C4") (pinfunction "RLDFB_C4") (pintype "passive"))
      (node (ref "R19") (pin "1") (pintype "passive"))
    )
    (net (code "46") (name "Net-(IC8-LBOOST)") (class "Default")
      (node (ref "IC8") (pin "20") (pinfunction "LBOOST_20") (pintype "passive"))
      (node (ref "L1") (pin "1") (pinfunction "1_1") (pintype "passive"))
    )
    (net (code "47") (name "Net-(IC8-LBUCK)") (class "Default")
      (node (ref "IC8") (pin "16") (pinfunction "LBUCK_16") (pintype "passive"))
      (node (ref "L2") (pin "1") (pinfunction "1_1") (pintype "passive"))
    )
    (net (code "48") (name "Net-(IC8-OK_HYST)") (class "Default")
      (node (ref "IC8") (pin "10") (pinfunction "OK_HYST_10") (pintype "passive"))
      (node (ref "ROK2") (pin "2") (pintype "passive"))
      (node (ref "ROK3") (pin "1") (pintype "passive"))
    )
    (net (code "49") (name "Net-(IC8-OK_PROG)") (class "Default")
      (node (ref "IC8") (pin "11") (pinfunction "OK_PROG_11") (pintype "passive"))
      (node (ref "ROK1") (pin "2") (pintype "passive"))
      (node (ref "ROK2") (pin "1") (pintype "passive"))
    )
    (net (code "50") (name "Net-(IC8-VBAT)") (class "Default")
      (node (ref "CBATT1") (pin "1") (pinfunction "1_1") (pintype "passive"))
      (node (ref "CBATT2") (pin "1") (pinfunction "1_1") (pintype "passive"))
      (node (ref "CBATT3") (pin "1") (pinfunction "1_1") (pintype "passive"))
      (node (ref "IC8") (pin "18") (pinfunction "VBAT_18") (pintype "passive"))
    )
    (net (code "51") (name "Net-(IC8-VBAT_OV)") (class "Default")
      (node (ref "IC8") (pin "7") (pinfunction "VBAT_OV_7") (pintype "passive"))
      (node (ref "ROV1") (pin "1") (pintype "passive"))
      (node (ref "ROV2") (pin "1") (pintype "passive"))
    )
    (net (code "52") (name "Net-(IC8-VOC_SAMP)") (class "Default")
      (node (ref "IC8") (pin "3") (pinfunction "VOC_SAMP_3") (pintype "passive"))
      (node (ref "ROC1") (pin "1") (pintype "passive"))
      (node (ref "ROC2") (pin "2") (pintype "passive"))
    )
    (net (code "53") (name "Net-(IC8-VOUT_EN)") (class "Default")
      (node (ref "IC8") (pin "6") (pinfunction "VOUT_EN_6") (pintype "passive"))
      (node (ref "P13") (pin "2") (pinfunction "2_2") (pintype "passive"))
    )
    (net (code "54") (name "Net-(IC8-VOUT_SET)") (class "Default")
      (node (ref "IC8") (pin "12") (pinfunction "VOUT_SET_12") (pintype "passive"))
      (node (ref "ROUT1") (pin "1") (pintype "passive"))
      (node (ref "ROUT2") (pin "1") (pintype "passive"))
    )
    (net (code "55") (name "Net-(IC8-VRDIV)") (class "Default")
      (node (ref "IC8") (pin "8") (pinfunction "VRDIV_8") (pintype "passive"))
      (node (ref "ROK3") (pin "2") (pintype "passive"))
      (node (ref "ROUT2") (pin "2") (pintype "passive"))
      (node (ref "ROV2") (pin "2") (pintype "passive"))
    )
    (net (code "56") (name "Net-(IC8-VREF_SAMP)") (class "Default")
      (node (ref "CREF") (pin "2") (pinfunction "2_2") (pintype "passive"))
      (node (ref "IC8") (pin "4") (pinfunction "VREF_SAMP_4") (pintype "passive"))
    )
    (net (code "57") (name "Net-(J2-Pad3)") (class "Default")
      (node (ref "J2") (pin "3") (pinfunction "3_3") (pintype "passive"))
      (node (ref "P7") (pin "3") (pinfunction "3_3") (pintype "passive"))
    )
    (net (code "58") (name "Net-(J2-Pad6)") (class "Default")
      (node (ref "J2") (pin "6") (pinfunction "6_6") (pintype "passive"))
      (node (ref "P7") (pin "6") (pinfunction "6_6") (pintype "passive"))
    )
    (net (code "59") (name "Net-(J2-Pad7)") (class "Default")
      (node (ref "J2") (pin "7") (pinfunction "7_7") (pintype "passive"))
      (node (ref "P7") (pin "7") (pinfunction "7_7") (pintype "passive"))
    )
    (net (code "60") (name "Net-(J2-Pad8)") (class "Default")
      (node (ref "J2") (pin "8") (pinfunction "8_8") (pintype "passive"))
      (node (ref "P7") (pin "8") (pinfunction "8_8") (pintype "passive"))
    )
    (net (code "61") (name "Net-(J2-Pad9)") (class "Default")
      (node (ref "J2") (pin "9") (pinfunction "9_9") (pintype "passive"))
      (node (ref "P7") (pin "9") (pinfunction "9_9") (pintype "passive"))
    )
    (net (code "62") (name "Net-(J2-Pad10)") (class "Default")
      (node (ref "J2") (pin "10") (pinfunction "10_10") (pintype "passive"))
      (node (ref "P7") (pin "10") (pinfunction "10_10") (pintype "passive"))
    )
    (net (code "63") (name "Net-(J2-Pad11)") (class "Default")
      (node (ref "J2") (pin "11") (pinfunction "11_11") (pintype "passive"))
      (node (ref "P7") (pin "11") (pinfunction "11_11") (pintype "passive"))
    )
    (net (code "64") (name "Net-(J2-Pad12)") (class "Default")
      (node (ref "J2") (pin "12") (pinfunction "12_12") (pintype "passive"))
      (node (ref "P7") (pin "12") (pinfunction "12_12") (pintype "passive"))
    )
    (net (code "65") (name "Net-(J2-Pad13)") (class "Default")
      (node (ref "J2") (pin "13") (pinfunction "13_13") (pintype "passive"))
      (node (ref "P7") (pin "13") (pinfunction "13_13") (pintype "passive"))
    )
    (net (code "66") (name "Net-(J2-Pad14)") (class "Default")
      (node (ref "J2") (pin "14") (pinfunction "14_14") (pintype "passive"))
      (node (ref "P7") (pin "14") (pinfunction "14_14") (pintype "passive"))
    )
    (net (code "67") (name "Net-(J2-Pad17)") (class "Default")
      (node (ref "J2") (pin "17") (pinfunction "17_17") (pintype "passive"))
      (node (ref "P7") (pin "17") (pinfunction "17_17") (pintype "passive"))
    )
    (net (code "68") (name "Net-(J2-Pad18)") (class "Default")
      (node (ref "J2") (pin "18") (pinfunction "18_18") (pintype "passive"))
      (node (ref "P7") (pin "18") (pinfunction "18_18") (pintype "passive"))
    )
    (net (code "69") (name "Net-(J2-Pad19)") (class "Default")
      (node (ref "J2") (pin "19") (pinfunction "19_19") (pintype "passive"))
      (node (ref "P7") (pin "19") (pinfunction "19_19") (pintype "passive"))
    )
    (net (code "70") (name "Net-(J2-Pad20)") (class "Default")
      (node (ref "J2") (pin "20") (pinfunction "20_20") (pintype "passive"))
      (node (ref "P7") (pin "20") (pinfunction "20_20") (pintype "passive"))
    )
    (net (code "71") (name "Net-(J2-Pad21)") (class "Default")
      (node (ref "J2") (pin "21") (pinfunction "21_21") (pintype "passive"))
      (node (ref "P7") (pin "21") (pinfunction "21_21") (pintype "passive"))
    )
    (net (code "72") (name "Net-(J2-Pad22)") (class "Default")
      (node (ref "J2") (pin "22") (pinfunction "22_22") (pintype "passive"))
      (node (ref "P7") (pin "22") (pinfunction "22_22") (pintype "passive"))
    )
    (net (code "73") (name "Net-(J2-Pad23)") (class "Default")
      (node (ref "J2") (pin "23") (pinfunction "23_23") (pintype "passive"))
      (node (ref "P7") (pin "23") (pinfunction "23_23") (pintype "passive"))
    )
    (net (code "74") (name "Net-(J3-Pad2)") (class "Default")
      (node (ref "J3") (pin "2") (pinfunction "2_2") (pintype "passive"))
      (node (ref "P8") (pin "1") (pinfunction "1_1") (pintype "passive"))
      (node (ref "R5") (pin "1") (pintype "passive"))
    )
    (net (code "75") (name "Net-(OSC1-Enable)") (class "Default")
      (node (ref "OSC1") (pin "1") (pinfunction "Enable_1") (pintype "passive"))
      (node (ref "P1") (pin "1") (pinfunction "1_1") (pintype "passive"))
    )
    (net (code "76") (name "Net-(Q1-D_1)") (class "Default")
      (node (ref "J5") (pin "1") (pinfunction "1_1") (pintype "passive"))
      (node (ref "P10") (pin "1") (pinfunction "1_1") (pintype "passive"))
      (node (ref "Q1") (pin "1") (pinfunction "D_1_1") (pintype "passive"))
      (node (ref "Q1") (pin "2") (pinfunction "D_2_2") (pintype "passive"))
      (node (ref "Q1") (pin "5") (pinfunction "D_3_5") (pintype "passive"))
      (node (ref "Q1") (pin "6") (pinfunction "D_4_6") (pintype "passive"))
    )
    (net (code "77") (name "Net-(R4-Pad2)") (class "Default")
      (node (ref "R4") (pin "2") (pintype "passive"))
      (node (ref "R5") (pin "2") (pintype "passive"))
      (node (ref "R6") (pin "1") (pintype "passive"))
    )
    (net (code "78") (name "unconnected-(IC4-NC-Pad1)") (class "Default")
      (node (ref "IC4") (pin "1") (pinfunction "NC_1") (pintype "passive+no_connect"))
    )
    (net (code "79") (name "unconnected-(IC6-NC_1-Pad1)") (class "Default")
      (node (ref "IC6") (pin "1") (pinfunction "NC_1_1") (pintype "passive+no_connect"))
    )
    (net (code "80") (name "unconnected-(IC6-NC_2-Pad4)") (class "Default")
      (node (ref "IC6") (pin "4") (pinfunction "NC_2_4") (pintype "passive+no_connect"))
    )
    (net (code "81") (name "unconnected-(IC6-~{SHDN}-Pad8)") (class "Default")
      (node (ref "IC6") (pin "8") (pinfunction "~{SHDN}_8") (pintype "passive+no_connect"))
    )
    (net (code "82") (name "unconnected-(IC7-SW-PadD4)") (class "Default")
      (node (ref "IC7") (pin "D4") (pinfunction "SW_D4") (pintype "passive+no_connect"))
    )
    (net (code "83") (name "unconnected-(IC8-NC_1-Pad9)") (class "Default")
      (node (ref "IC8") (pin "9") (pinfunction "NC_1_9") (pintype "passive+no_connect"))
    )
    (net (code "84") (name "unconnected-(IC8-NC_2-Pad17)") (class "Default")
      (node (ref "IC8") (pin "17") (pinfunction "NC_2_17") (pintype "passive+no_connect"))
    )
    (net (code "85") (name "unconnected-(J1-Pad1)") (class "Default")
      (node (ref "J1") (pin "1") (pinfunction "1_1") (pintype "passive"))
    )
    (net (code "86") (name "unconnected-(J1-Pad2)") (class "Default")
      (node (ref "J1") (pin "2") (pinfunction "2_2") (pintype "passive"))
    )
    (net (code "87") (name "unconnected-(J1-Pad3)") (class "Default")
      (node (ref "J1") (pin "3") (pinfunction "3_3") (pintype "passive"))
    )
    (net (code "88") (name "unconnected-(J1-Pad4)") (class "Default")
      (node (ref "J1") (pin "4") (pinfunction "4_4") (pintype "passive"))
    )
    (net (code "89") (name "unconnected-(J1-Pad5)") (class "Default")
      (node (ref "J1") (pin "5") (pinfunction "5_5") (pintype "passive"))
    )
    (net (code "90") (name "unconnected-(J1-Pad6)") (class "Default")
      (node (ref "J1") (pin "6") (pinfunction "6_6") (pintype "passive"))
    )
    (net (code "91") (name "unconnected-(J1-Pad7)") (class "Default")
      (node (ref "J1") (pin "7") (pinfunction "7_7") (pintype "passive"))
    )
    (net (code "92") (name "unconnected-(J1-Pad8)") (class "Default")
      (node (ref "J1") (pin "8") (pinfunction "8_8") (pintype "passive"))
    )
    (net (code "93") (name "unconnected-(J1-Pad9)") (class "Default")
      (node (ref "J1") (pin "9") (pinfunction "9_9") (pintype "passive"))
    )
    (net (code "94") (name "unconnected-(J1-Pad10)") (class "Default")
      (node (ref "J1") (pin "10") (pinfunction "10_10") (pintype "passive"))
    )
    (net (code "95") (name "unconnected-(J1-Pad11)") (class "Default")
      (node (ref "J1") (pin "11") (pinfunction "11_11") (pintype "passive"))
    )
    (net (code "96") (name "unconnected-(J1-Pad12)") (class "Default")
      (node (ref "J1") (pin "12") (pinfunction "12_12") (pintype "passive"))
    )
    (net (code "97") (name "unconnected-(J1-Pad13)") (class "Default")
      (node (ref "J1") (pin "13") (pinfunction "13_13") (pintype "passive"))
    )
    (net (code "98") (name "unconnected-(J1-Pad14)") (class "Default")
      (node (ref "J1") (pin "14") (pinfunction "14_14") (pintype "passive"))
    )
    (net (code "99") (name "unconnected-(J1-Pad15)") (class "Default")
      (node (ref "J1") (pin "15") (pinfunction "15_15") (pintype "passive"))
    )
    (net (code "100") (name "unconnected-(J1-Pad16)") (class "Default")
      (node (ref "J1") (pin "16") (pinfunction "16_16") (pintype "passive"))
    )
    (net (code "101") (name "unconnected-(J1-Pad17)") (class "Default")
      (node (ref "J1") (pin "17") (pinfunction "17_17") (pintype "passive"))
    )
    (net (code "102") (name "unconnected-(J1-Pad18)") (class "Default")
      (node (ref "J1") (pin "18") (pinfunction "18_18") (pintype "passive"))
    )
    (net (code "103") (name "unconnected-(J1-Pad19)") (class "Default")
      (node (ref "J1") (pin "19") (pinfunction "19_19") (pintype "passive"))
    )
    (net (code "104") (name "unconnected-(J1-Pad20)") (class "Default")
      (node (ref "J1") (pin "20") (pinfunction "20_20") (pintype "passive"))
    )
    (net (code "105") (name "unconnected-(J1-Pad21)") (class "Default")
      (node (ref "J1") (pin "21") (pinfunction "21_21") (pintype "passive"))
    )
    (net (code "106") (name "unconnected-(J1-Pad22)") (class "Default")
      (node (ref "J1") (pin "22") (pinfunction "22_22") (pintype "passive"))
    )
    (net (code "107") (name "unconnected-(J1-Pad23)") (class "Default")
      (node (ref "J1") (pin "23") (pinfunction "23_23") (pintype "passive"))
    )
    (net (code "108") (name "unconnected-(M1-Pad1)") (class "Default")
      (node (ref "M1") (pin "1") (pinfunction "1_1") (pintype "passive+no_connect"))
    )
    (net (code "109") (name "unconnected-(M2-Pad1)") (class "Default")
      (node (ref "M2") (pin "1") (pinfunction "1_1") (pintype "passive+no_connect"))
    )
    (net (code "110") (name "unconnected-(M3-Pad1)") (class "Default")
      (node (ref "M3") (pin "1") (pinfunction "1_1") (pintype "passive+no_connect"))
    )
    (net (code "111") (name "unconnected-(M4-Pad1)") (class "Default")
      (node (ref "M4") (pin "1") (pinfunction "1_1") (pintype "passive+no_connect"))
    )
  )
)
